# circuitdraft.net
KiCad netlist of a schematic drawn in EAGLE
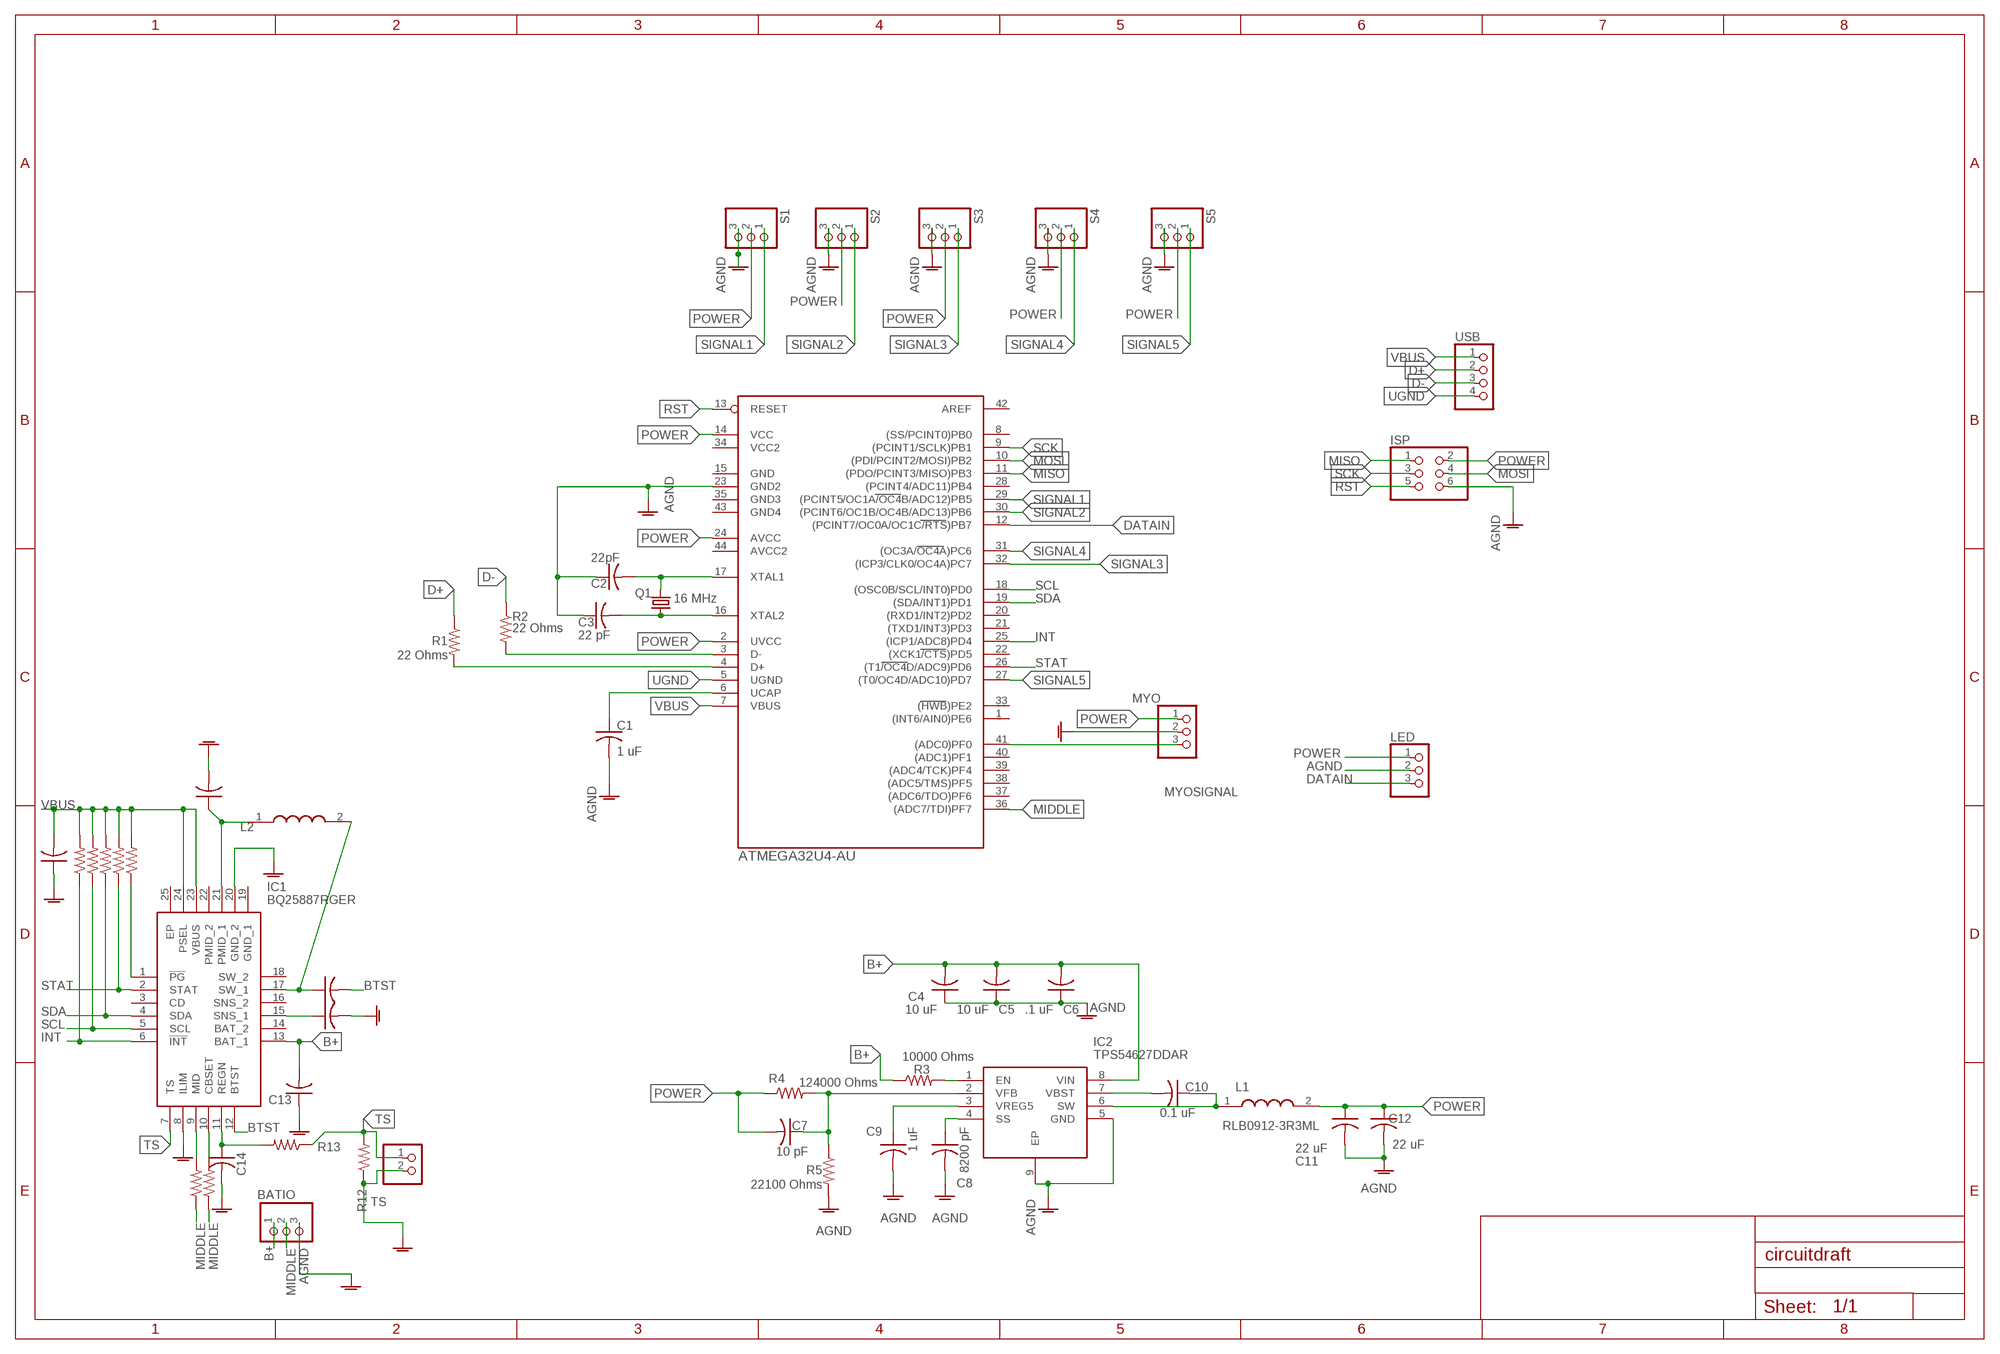
[diagram p0: schematic, sheet 1]

(export (version "E")
  (design (tool "Eeschema 10.0.6"))
  (components
    (comp (ref "BATIO")
      (value "PINHD-1X3")
      (footprint "eagle-import:1X03")
      (libsource (lib "eagle-import") (part "PINHD-1X3"))
    )
    (comp (ref "C1")
      (value "1 uF")
      (footprint "eagle-import:C0805")
      (libsource (lib "eagle-import") (part "C-USC0805"))
    )
    (comp (ref "C2")
      (value "22pF")
      (footprint "eagle-import:C0805")
      (libsource (lib "eagle-import") (part "C-USC0805"))
    )
    (comp (ref "C3")
      (value "22 pF")
      (footprint "eagle-import:C0805")
      (libsource (lib "eagle-import") (part "C-USC0805"))
    )
    (comp (ref "C4")
      (value "10 uF")
      (footprint "eagle-import:C0805")
      (libsource (lib "eagle-import") (part "C-USC0805"))
    )
    (comp (ref "C5")
      (value "10 uF")
      (footprint "eagle-import:C0805")
      (libsource (lib "eagle-import") (part "C-USC0805"))
    )
    (comp (ref "C6")
      (value ".1 uF")
      (footprint "eagle-import:C0805")
      (libsource (lib "eagle-import") (part "C-USC0805"))
    )
    (comp (ref "C7")
      (value "10 pF")
      (footprint "eagle-import:C0805")
      (libsource (lib "eagle-import") (part "C-USC0805"))
    )
    (comp (ref "C8")
      (value "8200 pF")
      (footprint "eagle-import:C0805")
      (libsource (lib "eagle-import") (part "C-USC0805"))
    )
    (comp (ref "C9")
      (value "1 uF")
      (footprint "eagle-import:C0805")
      (libsource (lib "eagle-import") (part "C-USC0805"))
    )
    (comp (ref "C10")
      (value "0.1 uF")
      (footprint "eagle-import:C0805")
      (libsource (lib "eagle-import") (part "C-USC0805"))
    )
    (comp (ref "C11")
      (value "22 uF")
      (footprint "eagle-import:C0805")
      (libsource (lib "eagle-import") (part "C-USC0805"))
    )
    (comp (ref "C12")
      (value "22 uF")
      (footprint "eagle-import:C0805")
      (libsource (lib "eagle-import") (part "C-USC0805"))
    )
    (comp (ref "C13")
      (value "1 uF")
      (footprint "eagle-import:C0805")
      (libsource (lib "eagle-import") (part "C-USC0805"))
    )
    (comp (ref "C14")
      (value "4.7 uF")
      (footprint "eagle-import:C0805")
      (libsource (lib "eagle-import") (part "C-USC0805"))
    )
    (comp (ref "C15")
      (value "47 nF")
      (footprint "eagle-import:C0805")
      (libsource (lib "eagle-import") (part "C-USC0805"))
    )
    (comp (ref "C16")
      (value "44 uF")
      (footprint "eagle-import:C0805")
      (libsource (lib "eagle-import") (part "C-USC0805"))
    )
    (comp (ref "C17")
      (value "1 uF")
      (footprint "eagle-import:C0805")
      (libsource (lib "eagle-import") (part "C-USC0805"))
    )
    (comp (ref "C18")
      (value "10 uF")
      (footprint "eagle-import:C0805")
      (libsource (lib "eagle-import") (part "C-USC0805"))
    )
    (comp (ref "IC1")
      (value "BQ25887RGER")
      (footprint "eagle-import:QFN50P400X400X100-25N")
      (fields (field (name "MOUSER_PART_NUMBER") "595-BQ25887RGER"))
      (libsource (lib "eagle-import") (part "BQ25887RGER"))
    )
    (comp (ref "IC2")
      (value "TPS54627DDAR")
      (footprint "eagle-import:SOIC127P600X170-9N")
      (fields (field (name "MOUSER_PART_NUMBER") "595-TPS54627DDAR"))
      (libsource (lib "eagle-import") (part "TPS54627DDAR"))
    )
    (comp (ref "ISP")
      (value "PINHD-2X3")
      (footprint "eagle-import:2X03")
      (libsource (lib "eagle-import") (part "PINHD-2X3"))
    )
    (comp (ref "L1")
      (value "RLB0912-3R3ML")
      (footprint "eagle-import:RLB0914")
      (fields (field (name "MOUSER_PART_NUMBER") "652-RLB0912-3R3ML"))
      (libsource (lib "eagle-import") (part "RLB0912-3R3ML"))
    )
    (comp (ref "L2")
      (value "1 uH")
      (footprint "eagle-import:INDC2016X100N")
      (fields
        (field (name "MANUFACTURER_PART_NUMBER") "TFM201610GHM-1R0MTAA")
        (field (name "MOUSER_PART_NUMBER") "810-TFM201610GHM1R0A")
      )
      (libsource (lib "eagle-import") (part "TFM201610GHM-1R0MTAA"))
    )
    (comp (ref "LED")
      (value "PINHD-1X3")
      (footprint "eagle-import:1X03")
      (libsource (lib "eagle-import") (part "PINHD-1X3"))
    )
    (comp (ref "MYO")
      (value "PINHD-1X3")
      (footprint "eagle-import:1X03")
      (libsource (lib "eagle-import") (part "PINHD-1X3"))
    )
    (comp (ref "Q1")
      (value "16 MHz")
      (footprint "eagle-import:HC49_S")
      (libsource (lib "eagle-import") (part "CRYSTALHC49S"))
    )
    (comp (ref "R1")
      (value "22 Ohms")
      (footprint "eagle-import:R0603")
      (libsource (lib "eagle-import") (part "R-US_R0603"))
    )
    (comp (ref "R2")
      (value "22 Ohms")
      (footprint "eagle-import:R0603")
      (libsource (lib "eagle-import") (part "R-US_R0603"))
    )
    (comp (ref "R3")
      (value "10000 Ohms")
      (footprint "eagle-import:R0603")
      (libsource (lib "eagle-import") (part "R-US_R0603"))
    )
    (comp (ref "R4")
      (value "124000 Ohms")
      (footprint "eagle-import:R0603")
      (libsource (lib "eagle-import") (part "R-US_R0603"))
    )
    (comp (ref "R5")
      (value "22100 Ohms")
      (footprint "eagle-import:R0603")
      (libsource (lib "eagle-import") (part "R-US_R0603"))
    )
    (comp (ref "R6")
      (value "12 Ohms")
      (footprint "eagle-import:R0603")
      (libsource (lib "eagle-import") (part "R-US_R0603"))
    )
    (comp (ref "R7")
      (value "10000 Ohms")
      (footprint "eagle-import:R0603")
      (libsource (lib "eagle-import") (part "R-US_R0603"))
    )
    (comp (ref "R8")
      (value "10000 Ohms")
      (footprint "eagle-import:R0603")
      (libsource (lib "eagle-import") (part "R-US_R0603"))
    )
    (comp (ref "R9")
      (value "10000 Ohms")
      (footprint "eagle-import:R0603")
      (libsource (lib "eagle-import") (part "R-US_R0603"))
    )
    (comp (ref "R10")
      (value "10000 Ohms")
      (footprint "eagle-import:R0603")
      (libsource (lib "eagle-import") (part "R-US_R0603"))
    )
    (comp (ref "R11")
      (value "10000 Ohms")
      (footprint "eagle-import:R0603")
      (libsource (lib "eagle-import") (part "R-US_R0603"))
    )
    (comp (ref "R12")
      (value "30.1 kOhms")
      (footprint "eagle-import:R0603")
      (libsource (lib "eagle-import") (part "R-US_R0603"))
    )
    (comp (ref "R13")
      (value "5.23 kOhms")
      (footprint "eagle-import:R0603")
      (libsource (lib "eagle-import") (part "R-US_R0603"))
    )
    (comp (ref "R14")
      (value "300 Ohms")
      (footprint "eagle-import:R0603")
      (libsource (lib "eagle-import") (part "R-US_R0603"))
    )
    (comp (ref "S1")
      (value "PINHD-1X3")
      (footprint "eagle-import:1X03")
      (libsource (lib "eagle-import") (part "PINHD-1X3"))
    )
    (comp (ref "S2")
      (value "PINHD-1X3")
      (footprint "eagle-import:1X03")
      (libsource (lib "eagle-import") (part "PINHD-1X3"))
    )
    (comp (ref "S3")
      (value "PINHD-1X3")
      (footprint "eagle-import:1X03")
      (libsource (lib "eagle-import") (part "PINHD-1X3"))
    )
    (comp (ref "S4")
      (value "PINHD-1X3")
      (footprint "eagle-import:1X03")
      (libsource (lib "eagle-import") (part "PINHD-1X3"))
    )
    (comp (ref "S5")
      (value "PINHD-1X3")
      (footprint "eagle-import:1X03")
      (libsource (lib "eagle-import") (part "PINHD-1X3"))
    )
    (comp (ref "TS")
      (value "PINHD-1X2")
      (footprint "eagle-import:1X02")
      (libsource (lib "eagle-import") (part "PINHD-1X2"))
    )
    (comp (ref "U$1")
      (value "ATMEGA32U4-AU")
      (footprint "eagle-import:TQFP44")
      (libsource (lib "eagle-import") (part "ATMEGA32U4-AU"))
    )
    (comp (ref "USB")
      (value "PINHD-1X4")
      (footprint "eagle-import:1X04")
      (libsource (lib "eagle-import") (part "PINHD-1X4"))
    )
  )
  (nets
    (net (code "1") (name "/BTST") (class "Default")
      (node (ref "C15") (pin "2") (pinfunction "2_2") (pintype "passive"))
      (node (ref "IC1") (pin "12") (pinfunction "BTST_12") (pintype "bidirectional"))
    )
    (net (code "2") (name "/INT") (class "Default")
      (node (ref "IC1") (pin "6") (pinfunction "~{INT}_6") (pintype "bidirectional"))
      (node (ref "R10") (pin "1") (pinfunction "1_1") (pintype "passive"))
      (node (ref "U$1") (pin "25") (pinfunction "(ICP1/ADC8)PD4_25") (pintype "bidirectional"))
    )
    (net (code "3") (name "/MYOSIGNAL") (class "Default")
      (node (ref "MYO") (pin "3") (pinfunction "3_3") (pintype "passive"))
      (node (ref "U$1") (pin "41") (pinfunction "(ADC0)PF0_41") (pintype "bidirectional"))
    )
    (net (code "4") (name "/SCL") (class "Default")
      (node (ref "IC1") (pin "5") (pinfunction "SCL_5") (pintype "bidirectional"))
      (node (ref "R8") (pin "1") (pinfunction "1_1") (pintype "passive"))
      (node (ref "U$1") (pin "18") (pinfunction "(OSC0B/SCL/INT0)PD0_18") (pintype "bidirectional"))
    )
    (net (code "5") (name "/SDA") (class "Default")
      (node (ref "IC1") (pin "4") (pinfunction "SDA_4") (pintype "bidirectional"))
      (node (ref "R7") (pin "1") (pinfunction "1_1") (pintype "passive"))
      (node (ref "U$1") (pin "19") (pinfunction "(SDA/INT1)PD1_19") (pintype "bidirectional"))
    )
    (net (code "6") (name "/STAT") (class "Default")
      (node (ref "IC1") (pin "2") (pinfunction "STAT_2") (pintype "bidirectional"))
      (node (ref "R11") (pin "1") (pinfunction "1_1") (pintype "passive"))
      (node (ref "U$1") (pin "26") (pinfunction "(T1/OC4D/ADC9)PD6_26") (pintype "bidirectional"))
    )
    (net (code "7") (name "AGND") (class "Default")
      (node (ref "BATIO") (pin "3") (pinfunction "3_3") (pintype "passive"))
      (node (ref "C1") (pin "2") (pinfunction "2_2") (pintype "passive"))
      (node (ref "C11") (pin "2") (pinfunction "2_2") (pintype "passive"))
      (node (ref "C12") (pin "2") (pinfunction "2_2") (pintype "passive"))
      (node (ref "C13") (pin "1") (pinfunction "1_1") (pintype "passive"))
      (node (ref "C14") (pin "2") (pinfunction "2_2") (pintype "passive"))
      (node (ref "C16") (pin "2") (pinfunction "2_2") (pintype "passive"))
      (node (ref "C17") (pin "1") (pinfunction "1_1") (pintype "passive"))
      (node (ref "C18") (pin "2") (pinfunction "2_2") (pintype "passive"))
      (node (ref "C2") (pin "1") (pinfunction "1_1") (pintype "passive"))
      (node (ref "C3") (pin "1") (pinfunction "1_1") (pintype "passive"))
      (node (ref "C4") (pin "1") (pinfunction "1_1") (pintype "passive"))
      (node (ref "C5") (pin "1") (pinfunction "1_1") (pintype "passive"))
      (node (ref "C6") (pin "1") (pinfunction "1_1") (pintype "passive"))
      (node (ref "C8") (pin "2") (pinfunction "2_2") (pintype "passive"))
      (node (ref "C9") (pin "2") (pinfunction "2_2") (pintype "passive"))
      (node (ref "IC1") (pin "20") (pinfunction "GND_2_20") (pintype "bidirectional"))
      (node (ref "IC1") (pin "8") (pinfunction "ILIM_8") (pintype "bidirectional"))
      (node (ref "IC2") (pin "5") (pinfunction "GND_5") (pintype "bidirectional"))
      (node (ref "IC2") (pin "9") (pinfunction "EP_9") (pintype "bidirectional"))
      (node (ref "ISP") (pin "6") (pinfunction "6_6") (pintype "passive"))
      (node (ref "LED") (pin "2") (pinfunction "2_2") (pintype "passive"))
      (node (ref "MYO") (pin "2") (pinfunction "2_2") (pintype "passive"))
      (node (ref "R12") (pin "1") (pinfunction "1_1") (pintype "passive"))
      (node (ref "R5") (pin "2") (pinfunction "2_2") (pintype "passive"))
      (node (ref "S1") (pin "3") (pinfunction "3_3") (pintype "passive"))
      (node (ref "S2") (pin "3") (pinfunction "3_3") (pintype "passive"))
      (node (ref "S3") (pin "3") (pinfunction "3_3") (pintype "passive"))
      (node (ref "S4") (pin "3") (pinfunction "3_3") (pintype "passive"))
      (node (ref "S5") (pin "3") (pinfunction "3_3") (pintype "passive"))
      (node (ref "TS") (pin "2") (pinfunction "2_2") (pintype "passive"))
      (node (ref "U$1") (pin "23") (pinfunction "GND2_23") (pintype "bidirectional"))
    )
    (net (code "8") (name "B+") (class "Default")
      (node (ref "BATIO") (pin "1") (pinfunction "1_1") (pintype "passive"))
      (node (ref "C13") (pin "2") (pinfunction "2_2") (pintype "passive"))
      (node (ref "C4") (pin "2") (pinfunction "2_2") (pintype "passive"))
      (node (ref "C5") (pin "2") (pinfunction "2_2") (pintype "passive"))
      (node (ref "C6") (pin "2") (pinfunction "2_2") (pintype "passive"))
      (node (ref "IC1") (pin "13") (pinfunction "BAT_1_13") (pintype "bidirectional"))
      (node (ref "IC2") (pin "8") (pinfunction "VIN_8") (pintype "bidirectional"))
      (node (ref "R3") (pin "1") (pinfunction "1_1") (pintype "passive"))
    )
    (net (code "9") (name "D+") (class "Default")
      (node (ref "R1") (pin "1") (pinfunction "1_1") (pintype "passive"))
      (node (ref "USB") (pin "2") (pinfunction "2_2") (pintype "passive"))
    )
    (net (code "10") (name "D-") (class "Default")
      (node (ref "R2") (pin "1") (pinfunction "1_1") (pintype "passive"))
      (node (ref "USB") (pin "3") (pinfunction "3_3") (pintype "passive"))
    )
    (net (code "11") (name "DATAIN") (class "Default")
      (node (ref "LED") (pin "3") (pinfunction "3_3") (pintype "passive"))
      (node (ref "U$1") (pin "12") (pinfunction "(PCINT7/OC0A/OC1C/RTS)PB7_12") (pintype "bidirectional"))
    )
    (net (code "12") (name "MIDDLE") (class "Default")
      (node (ref "BATIO") (pin "2") (pinfunction "2_2") (pintype "passive"))
      (node (ref "R14") (pin "1") (pinfunction "1_1") (pintype "passive"))
      (node (ref "R6") (pin "1") (pinfunction "1_1") (pintype "passive"))
      (node (ref "U$1") (pin "36") (pinfunction "(ADC7/TDI)PF7_36") (pintype "bidirectional"))
    )
    (net (code "13") (name "MISO") (class "Default")
      (node (ref "ISP") (pin "1") (pinfunction "1_1") (pintype "passive"))
      (node (ref "U$1") (pin "11") (pinfunction "(PDO/PCINT3/MISO)PB3_11") (pintype "bidirectional"))
    )
    (net (code "14") (name "MOSI") (class "Default")
      (node (ref "ISP") (pin "4") (pinfunction "4_4") (pintype "passive"))
      (node (ref "U$1") (pin "10") (pinfunction "(PDI/PCINT2/MOSI)PB2_10") (pintype "bidirectional"))
    )
    (net (code "15") (name "Net-(IC1-CBSET)") (class "Default")
      (node (ref "IC1") (pin "10") (pinfunction "CBSET_10") (pintype "bidirectional"))
      (node (ref "R6") (pin "2") (pinfunction "2_2") (pintype "passive"))
    )
    (net (code "16") (name "Net-(IC1-MID)") (class "Default")
      (node (ref "IC1") (pin "9") (pinfunction "MID_9") (pintype "bidirectional"))
      (node (ref "R14") (pin "2") (pinfunction "2_2") (pintype "passive"))
    )
    (net (code "17") (name "Net-(IC1-PMID_1)") (class "Default")
      (node (ref "C18") (pin "1") (pinfunction "1_1") (pintype "passive"))
      (node (ref "IC1") (pin "21") (pinfunction "PMID_1_21") (pintype "bidirectional"))
      (node (ref "L2") (pin "1") (pinfunction "1_1") (pintype "bidirectional"))
    )
    (net (code "18") (name "Net-(IC1-REGN)") (class "Default")
      (node (ref "C14") (pin "1") (pinfunction "1_1") (pintype "passive"))
      (node (ref "IC1") (pin "11") (pinfunction "REGN_11") (pintype "bidirectional"))
      (node (ref "R13") (pin "2") (pinfunction "2_2") (pintype "passive"))
    )
    (net (code "19") (name "Net-(IC1-SNS_1)") (class "Default")
      (node (ref "C16") (pin "1") (pinfunction "1_1") (pintype "passive"))
      (node (ref "IC1") (pin "15") (pinfunction "SNS_1_15") (pintype "bidirectional"))
    )
    (net (code "20") (name "Net-(IC1-SW_1)") (class "Default")
      (node (ref "C15") (pin "1") (pinfunction "1_1") (pintype "passive"))
      (node (ref "IC1") (pin "17") (pinfunction "SW_1_17") (pintype "bidirectional"))
      (node (ref "L2") (pin "2") (pinfunction "2_2") (pintype "bidirectional"))
    )
    (net (code "21") (name "Net-(IC1-~{PG})") (class "Default")
      (node (ref "IC1") (pin "1") (pinfunction "~{PG}_1") (pintype "bidirectional"))
      (node (ref "R9") (pin "1") (pinfunction "1_1") (pintype "passive"))
    )
    (net (code "22") (name "Net-(IC2-EN)") (class "Default")
      (node (ref "IC2") (pin "1") (pinfunction "EN_1") (pintype "bidirectional"))
      (node (ref "R3") (pin "2") (pinfunction "2_2") (pintype "passive"))
    )
    (net (code "23") (name "Net-(IC2-SS)") (class "Default")
      (node (ref "C8") (pin "1") (pinfunction "1_1") (pintype "passive"))
      (node (ref "IC2") (pin "4") (pinfunction "SS_4") (pintype "bidirectional"))
    )
    (net (code "24") (name "Net-(IC2-SW)") (class "Default")
      (node (ref "C10") (pin "1") (pinfunction "1_1") (pintype "passive"))
      (node (ref "IC2") (pin "6") (pinfunction "SW_6") (pintype "bidirectional"))
      (node (ref "L1") (pin "1") (pinfunction "1_1") (pintype "bidirectional"))
    )
    (net (code "25") (name "Net-(IC2-VBST)") (class "Default")
      (node (ref "C10") (pin "2") (pinfunction "2_2") (pintype "passive"))
      (node (ref "IC2") (pin "7") (pinfunction "VBST_7") (pintype "bidirectional"))
    )
    (net (code "26") (name "Net-(IC2-VFB)") (class "Default")
      (node (ref "C7") (pin "1") (pinfunction "1_1") (pintype "passive"))
      (node (ref "IC2") (pin "2") (pinfunction "VFB_2") (pintype "bidirectional"))
      (node (ref "R4") (pin "2") (pinfunction "2_2") (pintype "passive"))
      (node (ref "R5") (pin "1") (pinfunction "1_1") (pintype "passive"))
    )
    (net (code "27") (name "Net-(IC2-VREG5)") (class "Default")
      (node (ref "C9") (pin "1") (pinfunction "1_1") (pintype "passive"))
      (node (ref "IC2") (pin "3") (pinfunction "VREG5_3") (pintype "bidirectional"))
    )
    (net (code "28") (name "Net-(U$1-D+)") (class "Default")
      (node (ref "R1") (pin "2") (pinfunction "2_2") (pintype "passive"))
      (node (ref "U$1") (pin "4") (pinfunction "D+_4") (pintype "bidirectional"))
    )
    (net (code "29") (name "Net-(U$1-D-)") (class "Default")
      (node (ref "R2") (pin "2") (pinfunction "2_2") (pintype "passive"))
      (node (ref "U$1") (pin "3") (pinfunction "D-_3") (pintype "bidirectional"))
    )
    (net (code "30") (name "Net-(U$1-UCAP)") (class "Default")
      (node (ref "C1") (pin "1") (pinfunction "1_1") (pintype "passive"))
      (node (ref "U$1") (pin "6") (pinfunction "UCAP_6") (pintype "bidirectional"))
    )
    (net (code "31") (name "Net-(U$1-XTAL1)") (class "Default")
      (node (ref "C2") (pin "2") (pinfunction "2_2") (pintype "passive"))
      (node (ref "Q1") (pin "2") (pinfunction "2_2") (pintype "passive"))
      (node (ref "U$1") (pin "17") (pinfunction "XTAL1_17") (pintype "bidirectional"))
    )
    (net (code "32") (name "Net-(U$1-XTAL2)") (class "Default")
      (node (ref "C3") (pin "2") (pinfunction "2_2") (pintype "passive"))
      (node (ref "Q1") (pin "1") (pinfunction "1_1") (pintype "passive"))
      (node (ref "U$1") (pin "16") (pinfunction "XTAL2_16") (pintype "bidirectional"))
    )
    (net (code "33") (name "POWER") (class "Default")
      (node (ref "C11") (pin "1") (pinfunction "1_1") (pintype "passive"))
      (node (ref "C12") (pin "1") (pinfunction "1_1") (pintype "passive"))
      (node (ref "C7") (pin "2") (pinfunction "2_2") (pintype "passive"))
      (node (ref "ISP") (pin "2") (pinfunction "2_2") (pintype "passive"))
      (node (ref "L1") (pin "2") (pinfunction "2_2") (pintype "bidirectional"))
      (node (ref "LED") (pin "1") (pinfunction "1_1") (pintype "passive"))
      (node (ref "MYO") (pin "1") (pinfunction "1_1") (pintype "passive"))
      (node (ref "R4") (pin "1") (pinfunction "1_1") (pintype "passive"))
      (node (ref "S1") (pin "2") (pinfunction "2_2") (pintype "passive"))
      (node (ref "S2") (pin "2") (pinfunction "2_2") (pintype "passive"))
      (node (ref "S3") (pin "2") (pinfunction "2_2") (pintype "passive"))
      (node (ref "S4") (pin "2") (pinfunction "2_2") (pintype "passive"))
      (node (ref "S5") (pin "2") (pinfunction "2_2") (pintype "passive"))
      (node (ref "U$1") (pin "14") (pinfunction "VCC_14") (pintype "bidirectional"))
      (node (ref "U$1") (pin "2") (pinfunction "UVCC_2") (pintype "bidirectional"))
      (node (ref "U$1") (pin "24") (pinfunction "AVCC_24") (pintype "bidirectional"))
    )
    (net (code "34") (name "RST") (class "Default")
      (node (ref "ISP") (pin "5") (pinfunction "5_5") (pintype "passive"))
      (node (ref "U$1") (pin "13") (pinfunction "RESET_13") (pintype "bidirectional"))
    )
    (net (code "35") (name "SCK") (class "Default")
      (node (ref "ISP") (pin "3") (pinfunction "3_3") (pintype "passive"))
      (node (ref "U$1") (pin "9") (pinfunction "(PCINT1/SCLK)PB1_9") (pintype "bidirectional"))
    )
    (net (code "36") (name "SIGNAL1") (class "Default")
      (node (ref "S1") (pin "1") (pinfunction "1_1") (pintype "passive"))
      (node (ref "U$1") (pin "29") (pinfunction "(PCINT5/OC1A/OC4B/ADC12)PB5_29") (pintype "bidirectional"))
    )
    (net (code "37") (name "SIGNAL2") (class "Default")
      (node (ref "S2") (pin "1") (pinfunction "1_1") (pintype "passive"))
      (node (ref "U$1") (pin "30") (pinfunction "(PCINT6/OC1B/OC4B/ADC13)PB6_30") (pintype "bidirectional"))
    )
    (net (code "38") (name "SIGNAL3") (class "Default")
      (node (ref "S3") (pin "1") (pinfunction "1_1") (pintype "passive"))
      (node (ref "U$1") (pin "32") (pinfunction "(ICP3/CLK0/OC4A)PC7_32") (pintype "bidirectional"))
    )
    (net (code "39") (name "SIGNAL4") (class "Default")
      (node (ref "S4") (pin "1") (pinfunction "1_1") (pintype "passive"))
      (node (ref "U$1") (pin "31") (pinfunction "(OC3A/OC4A)PC6_31") (pintype "bidirectional"))
    )
    (net (code "40") (name "SIGNAL5") (class "Default")
      (node (ref "S5") (pin "1") (pinfunction "1_1") (pintype "passive"))
      (node (ref "U$1") (pin "27") (pinfunction "(T0/OC4D/ADC10)PD7_27") (pintype "bidirectional"))
    )
    (net (code "41") (name "TS") (class "Default")
      (node (ref "IC1") (pin "7") (pinfunction "TS_7") (pintype "bidirectional"))
      (node (ref "R12") (pin "2") (pinfunction "2_2") (pintype "passive"))
      (node (ref "R13") (pin "1") (pinfunction "1_1") (pintype "passive"))
      (node (ref "TS") (pin "1") (pinfunction "1_1") (pintype "passive"))
    )
    (net (code "42") (name "UGND") (class "Default")
      (node (ref "U$1") (pin "5") (pinfunction "UGND_5") (pintype "bidirectional"))
      (node (ref "USB") (pin "4") (pinfunction "4_4") (pintype "passive"))
    )
    (net (code "43") (name "VBUS") (class "Default")
      (node (ref "C17") (pin "2") (pinfunction "2_2") (pintype "passive"))
      (node (ref "IC1") (pin "23") (pinfunction "VBUS_23") (pintype "bidirectional"))
      (node (ref "IC1") (pin "24") (pinfunction "PSEL_24") (pintype "bidirectional"))
      (node (ref "R10") (pin "2") (pinfunction "2_2") (pintype "passive"))
      (node (ref "R11") (pin "2") (pinfunction "2_2") (pintype "passive"))
      (node (ref "R7") (pin "2") (pinfunction "2_2") (pintype "passive"))
      (node (ref "R8") (pin "2") (pinfunction "2_2") (pintype "passive"))
      (node (ref "R9") (pin "2") (pinfunction "2_2") (pintype "passive"))
      (node (ref "U$1") (pin "7") (pinfunction "VBUS_7") (pintype "bidirectional"))
      (node (ref "USB") (pin "1") (pinfunction "1_1") (pintype "passive"))
    )
    (net (code "44") (name "unconnected-(IC1-BAT_2-Pad14)") (class "Default")
      (node (ref "IC1") (pin "14") (pinfunction "BAT_2_14") (pintype "bidirectional"))
    )
    (net (code "45") (name "unconnected-(IC1-CD-Pad3)") (class "Default")
      (node (ref "IC1") (pin "3") (pinfunction "CD_3") (pintype "bidirectional"))
    )
    (net (code "46") (name "unconnected-(IC1-EP-Pad25)") (class "Default")
      (node (ref "IC1") (pin "25") (pinfunction "EP_25") (pintype "bidirectional"))
    )
    (net (code "47") (name "unconnected-(IC1-GND_1-Pad19)") (class "Default")
      (node (ref "IC1") (pin "19") (pinfunction "GND_1_19") (pintype "bidirectional"))
    )
    (net (code "48") (name "unconnected-(IC1-PMID_2-Pad22)") (class "Default")
      (node (ref "IC1") (pin "22") (pinfunction "PMID_2_22") (pintype "bidirectional"))
    )
    (net (code "49") (name "unconnected-(IC1-SNS_2-Pad16)") (class "Default")
      (node (ref "IC1") (pin "16") (pinfunction "SNS_2_16") (pintype "bidirectional"))
    )
    (net (code "50") (name "unconnected-(IC1-SW_2-Pad18)") (class "Default")
      (node (ref "IC1") (pin "18") (pinfunction "SW_2_18") (pintype "bidirectional"))
    )
    (net (code "51") (name "unconnected-(U$1-(ADC1)PF1-Pad40)") (class "Default")
      (node (ref "U$1") (pin "40") (pinfunction "(ADC1)PF1_40") (pintype "bidirectional"))
    )
    (net (code "52") (name "unconnected-(U$1-(ADC4{slash}TCK)PF4-Pad39)") (class "Default")
      (node (ref "U$1") (pin "39") (pinfunction "(ADC4/TCK)PF4_39") (pintype "bidirectional"))
    )
    (net (code "53") (name "unconnected-(U$1-(ADC5{slash}TMS)PF5-Pad38)") (class "Default")
      (node (ref "U$1") (pin "38") (pinfunction "(ADC5/TMS)PF5_38") (pintype "bidirectional"))
    )
    (net (code "54") (name "unconnected-(U$1-(ADC6{slash}TDO)PF6-Pad37)") (class "Default")
      (node (ref "U$1") (pin "37") (pinfunction "(ADC6/TDO)PF6_37") (pintype "bidirectional"))
    )
    (net (code "55") (name "unconnected-(U$1-(HWB)PE2-Pad33)") (class "Default")
      (node (ref "U$1") (pin "33") (pinfunction "(HWB)PE2_33") (pintype "bidirectional"))
    )
    (net (code "56") (name "unconnected-(U$1-(INT6{slash}AIN0)PE6-Pad1)") (class "Default")
      (node (ref "U$1") (pin "1") (pinfunction "(INT6/AIN0)PE6_1") (pintype "bidirectional"))
    )
    (net (code "57") (name "unconnected-(U$1-(PCINT4{slash}ADC11)PB4-Pad28)") (class "Default")
      (node (ref "U$1") (pin "28") (pinfunction "(PCINT4/ADC11)PB4_28") (pintype "bidirectional"))
    )
    (net (code "58") (name "unconnected-(U$1-(RXD1{slash}INT2)PD2-Pad20)") (class "Default")
      (node (ref "U$1") (pin "20") (pinfunction "(RXD1/INT2)PD2_20") (pintype "bidirectional"))
    )
    (net (code "59") (name "unconnected-(U$1-(SS{slash}PCINT0)PB0-Pad8)") (class "Default")
      (node (ref "U$1") (pin "8") (pinfunction "(SS/PCINT0)PB0_8") (pintype "bidirectional"))
    )
    (net (code "60") (name "unconnected-(U$1-(TXD1{slash}INT3)PD3-Pad21)") (class "Default")
      (node (ref "U$1") (pin "21") (pinfunction "(TXD1/INT3)PD3_21") (pintype "bidirectional"))
    )
    (net (code "61") (name "unconnected-(U$1-(XCK1{slash}CTS)PD5-Pad22)") (class "Default")
      (node (ref "U$1") (pin "22") (pinfunction "(XCK1/CTS)PD5_22") (pintype "bidirectional"))
    )
    (net (code "62") (name "unconnected-(U$1-AREF-Pad42)") (class "Default")
      (node (ref "U$1") (pin "42") (pinfunction "AREF_42") (pintype "bidirectional"))
    )
    (net (code "63") (name "unconnected-(U$1-AVCC2-Pad44)") (class "Default")
      (node (ref "U$1") (pin "44") (pinfunction "AVCC2_44") (pintype "bidirectional"))
    )
    (net (code "64") (name "unconnected-(U$1-GND-Pad15)") (class "Default")
      (node (ref "U$1") (pin "15") (pinfunction "GND_15") (pintype "bidirectional"))
    )
    (net (code "65") (name "unconnected-(U$1-GND3-Pad35)") (class "Default")
      (node (ref "U$1") (pin "35") (pinfunction "GND3_35") (pintype "bidirectional"))
    )
    (net (code "66") (name "unconnected-(U$1-GND4-Pad43)") (class "Default")
      (node (ref "U$1") (pin "43") (pinfunction "GND4_43") (pintype "bidirectional"))
    )
    (net (code "67") (name "unconnected-(U$1-VCC2-Pad34)") (class "Default")
      (node (ref "U$1") (pin "34") (pinfunction "VCC2_34") (pintype "bidirectional"))
    )
  )
)
